# Power_Board.net
KiCad netlist of a schematic drawn in Altium Designer
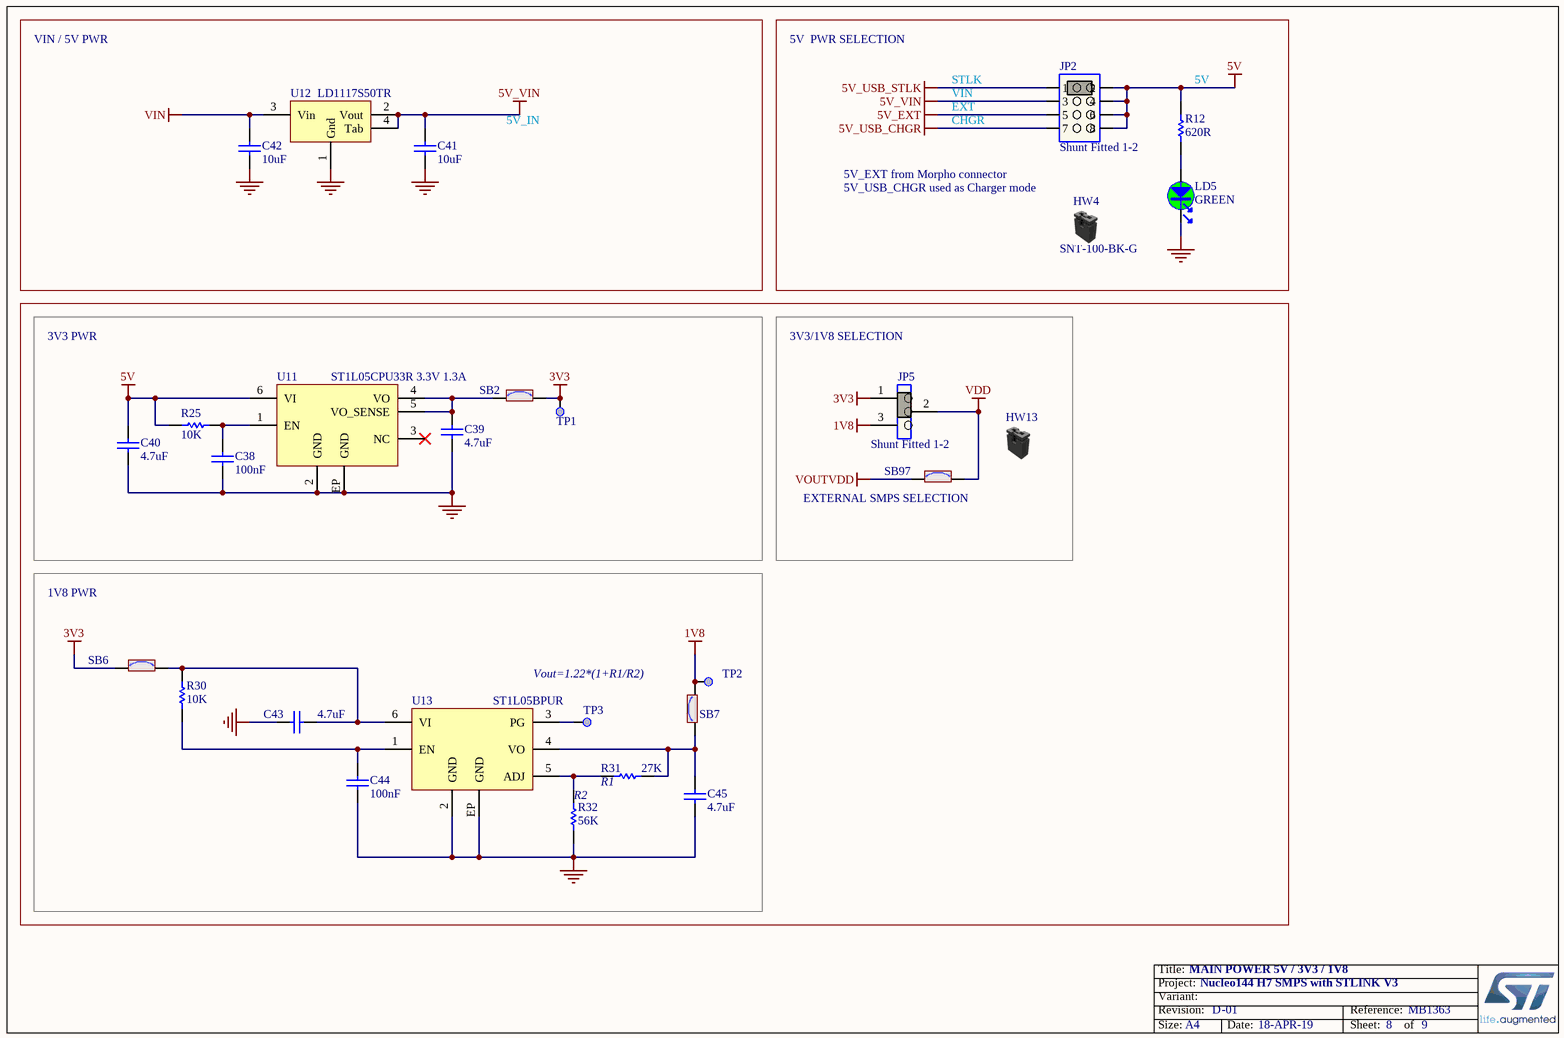
[diagram p0: Power_Board.SchDoc]

(export (version "E")
  (design (tool "Eeschema 10.0.6"))
  (components
    (comp (ref "C38")
      (value "100nF")
      (footprint "C0402")
      (description "Capacitor, MLCC, 100nF, 16V, X7R, 10%, 0402, T=0.5mm")
      (fields
        (field (name "INTERNAL_PART_NUMBER") "MCD-00006")
        (field (name "MANUFACTURER_PART_NUMBER") "CC0402KRX7R7BB104")
        (field (name "PROVIDED_BY") "SUBCO")
      )
      (libsource (lib "MCD_PARTS_database") (part "Capacitor"))
    )
    (comp (ref "C39")
      (value "4.7uF")
      (footprint "C0603")
      (description "Capacitor, MLCC, 4.7µF, 10V, X5R, 20%, 0603, T=0,8mm")
      (fields
        (field (name "INTERNAL_PART_NUMBER") "MCD-01121")
        (field (name "MANUFACTURER_PART_NUMBER") "GRM188R61A475ME15")
        (field (name "PROVIDED_BY") "SUBCO")
      )
      (libsource (lib "MCD_PARTS_database") (part "Capacitor"))
    )
    (comp (ref "C40")
      (value "4.7uF")
      (footprint "C0603")
      (description "Capacitor, MLCC, 4.7uF, 16V, X5R, 20%, 0603, T=0,8mm")
      (fields
        (field (name "INTERNAL_PART_NUMBER") "MCD-00097")
        (field (name "MANUFACTURER_PART_NUMBER") "GRM188R61C475KE11")
        (field (name "PROVIDED_BY") "SUBCO")
      )
      (libsource (lib "MCD_PARTS_database") (part "Capacitor"))
    )
    (comp (ref "C41")
      (value "10uF")
      (footprint "C0805")
      (description "Capacitor, MLCC, 10uF, 25V, X5R, 10%, 0805, T=0,85mm")
      (fields
        (field (name "INTERNAL_PART_NUMBER") "MCD-00014")
        (field (name "MANUFACTURER_PART_NUMBER") "CC0805KRX5R8BB106")
        (field (name "PROVIDED_BY") "SUBCO")
      )
      (libsource (lib "MCD_PARTS_database") (part "Capacitor"))
    )
    (comp (ref "C42")
      (value "10uF")
      (footprint "C0805")
      (description "Capacitor, MLCC, 10uF, 25V, X5R, 10%, 0805, T=0,85mm")
      (fields
        (field (name "INTERNAL_PART_NUMBER") "MCD-00014")
        (field (name "MANUFACTURER_PART_NUMBER") "CC0805KRX5R8BB106")
        (field (name "PROVIDED_BY") "SUBCO")
      )
      (libsource (lib "MCD_PARTS_database") (part "Capacitor"))
    )
    (comp (ref "C43")
      (value "4.7uF")
      (footprint "C0603")
      (description "Capacitor, MLCC, 4.7µF, 10V, X5R, 20%, 0603, T=0,8mm")
      (fields
        (field (name "INTERNAL_PART_NUMBER") "MCD-01121")
        (field (name "MANUFACTURER_PART_NUMBER") "GRM188R61A475ME15")
        (field (name "PROVIDED_BY") "SUBCO")
      )
      (libsource (lib "MCD_PARTS_database") (part "Capacitor"))
    )
    (comp (ref "C44")
      (value "100nF")
      (footprint "C0402")
      (description "Capacitor, MLCC, 100nF, 16V, X7R, 10%, 0402, T=0.5mm")
      (fields
        (field (name "INTERNAL_PART_NUMBER") "MCD-00006")
        (field (name "MANUFACTURER_PART_NUMBER") "CC0402KRX7R7BB104")
        (field (name "PROVIDED_BY") "SUBCO")
      )
      (libsource (lib "MCD_PARTS_database") (part "Capacitor"))
    )
    (comp (ref "C45")
      (value "4.7uF")
      (footprint "C0603")
      (description "Capacitor, MLCC, 4.7µF, 10V, X5R, 20%, 0603, T=0,8mm")
      (fields
        (field (name "INTERNAL_PART_NUMBER") "MCD-01121")
        (field (name "MANUFACTURER_PART_NUMBER") "GRM188R61A475ME15")
        (field (name "PROVIDED_BY") "SUBCO")
      )
      (libsource (lib "MCD_PARTS_database") (part "Capacitor"))
    )
    (comp (ref "HW4")
      (value "SNT-100-BK-G")
      (description "SHUNT 2.54mm BLACK")
      (fields
        (field (name "INTERNAL_PART_NUMBER") "MCD-00043")
        (field (name "MANUFACTURER") "SAMTEC")
        (field (name "PROVIDED_BY") "SUBCO")
      )
      (libsource (lib "MCD_PARTS_database") (part "Shunt Black 2.54mm"))
    )
    (comp (ref "HW13")
      (value "Shunt Black 2.54mm")
      (description "SHUNT 2.54mm BLACK")
      (fields
        (field (name "INTERNAL_PART_NUMBER") "MCD-00043")
        (field (name "MANUFACTURER_PART_NUMBER") "SNT-100-BK-G")
        (field (name "PROVIDED_BY") "SUBCO")
      )
      (libsource (lib "MCD_PARTS_database") (part "Shunt Black 2.54mm"))
    )
    (comp (ref "JP2")
      (value "Shunt Fitted 1-2")
      (footprint "CON_SAMTEC_TSW-104-07-X-D")
      (description "Header, 4x2, 2,54mm, VR, TH, Height 5.84mm/2.54mm - Shunt Fitted 1-2")
      (fields
        (field (name "INTERNAL_PART_NUMBER") "MCD-00686")
        (field (name "MANUFACTURER_PART_NUMBER") "TSW-104-07-x-D")
        (field (name "PROVIDED_BY") "SUBCO")
      )
      (libsource (lib "MCD_PARTS_database") (part "Jumper_Header 4x2 Fitted 1-2"))
    )
    (comp (ref "JP5")
      (value "Shunt Fitted 1-2")
      (footprint "CON_SAMTEC_TSW-103-07-F-S")
      (description "Header, 3x1, 2,54mm, VR, TH, Height 5.84mm/2.54mm - Shunt Fitted 1-2 by default")
      (fields
        (field (name "INTERNAL_PART_NUMBER") "MCD-00684")
        (field (name "MANUFACTURER_PART_NUMBER") "TSW-103-07-F-S")
        (field (name "PROVIDED_BY") "SUBCO")
      )
      (libsource (lib "MCD_PARTS_database") (part "Jumper_Header 3x1 Fitted 1-2"))
    )
    (comp (ref "LD5")
      (value "GREEN")
      (footprint "LED_0603_OSRAM_LG-Q396-PS-35_GREEN_1A2K_H0P4")
      (description "LED Green, 0603 SMD, Forward Voltage Typ=2V, Max=2.5V")
      (fields
        (field (name "INTERNAL_PART_NUMBER") "MCD-00588")
        (field (name "MANUFACTURER_PART_NUMBER") "LG Q396-PS-35")
        (field (name "PROVIDED_BY") "SUBCO")
      )
      (libsource (lib "MCD_PARTS_database") (part "LED_green"))
    )
    (comp (ref "R12")
      (value "620R")
      (footprint "R0603")
      (description "Resistor,620R,0603,1%,1/10W")
      (fields
        (field (name "INTERNAL_PART_NUMBER") "MCD-00500")
        (field (name "MANUFACTURER_PART_NUMBER") "RC0603FR-07620RL")
        (field (name "PROVIDED_BY") "SUBCO")
      )
      (libsource (lib "MCD_PARTS_database") (part "Resistor"))
    )
    (comp (ref "R25")
      (value "10K")
      (footprint "R0402")
      (description "Resistor,10K,0402,1%,1/16W")
      (fields
        (field (name "INTERNAL_PART_NUMBER") "MCD-00053")
        (field (name "MANUFACTURER_PART_NUMBER") "RC0402FR-0710KL")
        (field (name "PROVIDED_BY") "SUBCO")
      )
      (libsource (lib "MCD_PARTS_database") (part "Resistor"))
    )
    (comp (ref "R30")
      (value "10K")
      (footprint "R0402")
      (description "Resistor,10K,0402,1%,1/16W")
      (fields
        (field (name "INTERNAL_PART_NUMBER") "MCD-00053")
        (field (name "MANUFACTURER_PART_NUMBER") "RC0402FR-0710KL")
        (field (name "PROVIDED_BY") "SUBCO")
      )
      (libsource (lib "MCD_PARTS_database") (part "Resistor"))
    )
    (comp (ref "R31")
      (value "27K")
      (footprint "R0402")
      (description "Resistor,27K,0402,1%,1/16W")
      (fields
        (field (name "INTERNAL_PART_NUMBER") "MCD-00443")
        (field (name "MANUFACTURER_PART_NUMBER") "RC0402FR-0727KL")
        (field (name "PROVIDED_BY") "SUBCO")
      )
      (libsource (lib "MCD_PARTS_database") (part "Resistor"))
    )
    (comp (ref "R32")
      (value "56K")
      (footprint "R0402")
      (description "Resistor,56K,0402,1%,1/16W")
      (fields
        (field (name "INTERNAL_PART_NUMBER") "MCD-00493")
        (field (name "MANUFACTURER_PART_NUMBER") "RC0402FR-0756KL")
        (field (name "PROVIDED_BY") "SUBCO")
      )
      (libsource (lib "MCD_PARTS_database") (part "Resistor"))
    )
    (comp (ref "SB2")
      (value "SB_ON")
      (footprint "SOLDER-BRIDGE_R0603-0R")
      (description "Solder Bridge ON")
      (fields
        (field (name "INTERNAL_PART_NUMBER") "MCD-00071")
        (field (name "MANUFACTURER_PART_NUMBER") "RC0603JR-070RL")
        (field (name "PROVIDED_BY") "SUBCO")
      )
      (libsource (lib "MCD_PARTS_database") (part "SB_ON"))
    )
    (comp (ref "SB6")
      (value "SB_ON")
      (footprint "SOLDER-BRIDGE_R0603-0R")
      (description "Solder Bridge ON")
      (fields
        (field (name "INTERNAL_PART_NUMBER") "MCD-00071")
        (field (name "MANUFACTURER_PART_NUMBER") "RC0603JR-070RL")
        (field (name "PROVIDED_BY") "SUBCO")
      )
      (libsource (lib "MCD_PARTS_database") (part "SB_ON"))
    )
    (comp (ref "SB7")
      (value "SB_ON")
      (footprint "SOLDER-BRIDGE_R0603-0R")
      (description "Solder Bridge ON")
      (fields
        (field (name "INTERNAL_PART_NUMBER") "MCD-00071")
        (field (name "MANUFACTURER_PART_NUMBER") "RC0603JR-070RL")
        (field (name "PROVIDED_BY") "SUBCO")
      )
      (libsource (lib "") (part "SB_ON_1"))
    )
    (comp (ref "SB97")
      (value "SB_ON")
      (footprint "SOLDER-BRIDGE_R0603-0R")
      (description "Solder Bridge ON")
      (fields
        (field (name "INTERNAL_PART_NUMBER") "MCD-00071")
        (field (name "MANUFACTURER_PART_NUMBER") "RC0603JR-070RL")
        (field (name "PROVIDED_BY") "SUBCO")
      )
      (libsource (lib "MCD_PARTS_database") (part "SB_ON"))
    )
    (comp (ref "TP1")
      (value "Test Point")
      (footprint "TP_SMD_1MM")
      (description "Test Point 1mm")
      (fields (field (name "INTERNAL_PART_NUMBER") "MCD-00074") (field (name "MANUFACTURER") "n/a"))
      (libsource (lib "MCD_PARTS_database") (part "Test Point"))
    )
    (comp (ref "TP2")
      (value "Test Point")
      (footprint "TP_SMD_1MM")
      (description "Test Point 1mm")
      (fields
        (field (name "INTERNAL_PART_NUMBER") "MCD-00074")
        (field (name "MANUFACTURER_PART_NUMBER") "n/a")
      )
      (libsource (lib "") (part "Test Point_1"))
    )
    (comp (ref "TP3")
      (value "Test Point")
      (footprint "TP_SMD_1MM")
      (description "Test Point 1mm")
      (fields (field (name "INTERNAL_PART_NUMBER") "MCD-00074") (field (name "MANUFACTURER") "n/a"))
      (libsource (lib "") (part "Test Point_1"))
    )
    (comp (ref "U11")
      (value "ST1L05CPU33R 3.3V 1.3A")
      (footprint "ICC_DFN6-EPAD_3X3_P095")
      (description "LDO, 3.3V, 1.3A, Very low quiescent current BiCMOS voltage regulator")
      (fields
        (field (name "INTERNAL_PART_NUMBER") "MCD-01025")
        (field (name "MANUFACTURER_PART_NUMBER") "ST1L05CPU33R")
        (field (name "PROVIDED_BY") "SUBCO with ST control")
      )
      (libsource (lib "MCD_PARTS_database") (part "ST1L05CPU33R"))
    )
    (comp (ref "U12")
      (value "LD1117S50TR")
      (footprint "REG_SOT223-TAB")
      (description "IC REG LDO 5V 0.8A SOT223")
      (fields
        (field (name "INTERNAL_PART_NUMBER") "MCD-00088")
        (field (name "MANUFACTURER") "STMICROELECTRONICS")
        (field (name "PROVIDED_BY") "SUBCO with ST control")
      )
      (libsource (lib "MCD_PARTS_database") (part "LD1117S50TR"))
    )
    (comp (ref "U13")
      (value "ST1L05BPUR")
      (footprint "ICC_DFN6-EPAD_3X3_P095")
      (description "LDO Linear Voltage Regulator IC Positive Adjustable 1 Output Adjustable 1.3A 6-DFN (3x3)")
      (fields
        (field (name "INTERNAL_PART_NUMBER") "MCD-00581")
        (field (name "MANUFACTURER") "STMICROELECTRONICS")
        (field (name "PROVIDED_BY") "SUBCO with ST control")
      )
      (libsource (lib "MCD_PARTS_database") (part "ST1L05BPUR"))
    )
  )
  (nets
    (net (code "1") (name "1V8") (class "Default")
      (node (ref "JP5") (pin "3") (pinfunction "3_3") (pintype "passive"))
      (node (ref "SB7") (pin "2") (pinfunction "2_2") (pintype "passive"))
      (node (ref "TP2") (pin "1") (pinfunction "1_1") (pintype "passive"))
    )
    (net (code "2") (name "3V3") (class "Default")
      (node (ref "JP5") (pin "1") (pinfunction "1_1") (pintype "passive"))
      (node (ref "SB2") (pin "2") (pinfunction "2_2") (pintype "passive"))
      (node (ref "SB6") (pin "1") (pinfunction "1_1") (pintype "passive"))
      (node (ref "TP1") (pin "1") (pinfunction "1_1") (pintype "passive"))
    )
    (net (code "3") (name "5V") (class "Default")
      (node (ref "C40") (pin "2") (pinfunction "2_2") (pintype "passive"))
      (node (ref "JP2") (pin "2") (pinfunction "2_2") (pintype "passive"))
      (node (ref "JP2") (pin "4") (pinfunction "4_4") (pintype "passive"))
      (node (ref "JP2") (pin "6") (pinfunction "6_6") (pintype "passive"))
      (node (ref "JP2") (pin "8") (pinfunction "8_8") (pintype "passive"))
      (node (ref "R12") (pin "2") (pinfunction "2_2") (pintype "passive"))
      (node (ref "R25") (pin "2") (pinfunction "2_2") (pintype "passive"))
      (node (ref "U11") (pin "6") (pinfunction "VI_6") (pintype "passive"))
    )
    (net (code "4") (name "5V_EXT") (class "Default")
      (node (ref "JP2") (pin "5") (pinfunction "5_5") (pintype "passive"))
    )
    (net (code "5") (name "5V_USB_CHGR") (class "Default")
      (node (ref "JP2") (pin "7") (pinfunction "7_7") (pintype "passive"))
    )
    (net (code "6") (name "5V_USB_STLK") (class "Default")
      (node (ref "JP2") (pin "1") (pinfunction "1_1") (pintype "passive"))
    )
    (net (code "7") (name "5V_VIN") (class "Default")
      (node (ref "C41") (pin "2") (pinfunction "2_2") (pintype "passive"))
      (node (ref "JP2") (pin "3") (pinfunction "3_3") (pintype "passive"))
      (node (ref "U12") (pin "2") (pinfunction "Vout_2") (pintype "passive"))
      (node (ref "U12") (pin "4") (pinfunction "Tab_4") (pintype "passive"))
    )
    (net (code "8") (name "GND") (class "Default")
      (node (ref "C38") (pin "2") (pinfunction "2_2") (pintype "passive"))
      (node (ref "C39") (pin "1") (pinfunction "1_1") (pintype "passive"))
      (node (ref "C40") (pin "1") (pinfunction "1_1") (pintype "passive"))
      (node (ref "C41") (pin "1") (pinfunction "1_1") (pintype "passive"))
      (node (ref "C42") (pin "1") (pinfunction "1_1") (pintype "passive"))
      (node (ref "C43") (pin "2") (pinfunction "2_2") (pintype "passive"))
      (node (ref "C44") (pin "2") (pinfunction "2_2") (pintype "passive"))
      (node (ref "C45") (pin "1") (pinfunction "1_1") (pintype "passive"))
      (node (ref "LD5") (pin "2") (pintype "passive"))
      (node (ref "R32") (pin "1") (pinfunction "1_1") (pintype "passive"))
      (node (ref "U11") (pin "2") (pinfunction "GND_2") (pintype "passive"))
      (node (ref "U11") (pin "EP") (pinfunction "GND_EP") (pintype "passive"))
      (node (ref "U12") (pin "1") (pinfunction "Gnd_1") (pintype "passive"))
      (node (ref "U13") (pin "2") (pinfunction "GND_2") (pintype "passive"))
      (node (ref "U13") (pin "EP") (pinfunction "GND_EP") (pintype "passive"))
    )
    (net (code "9") (name "Net-(LD5-Pad1)") (class "Default")
      (node (ref "LD5") (pin "1") (pintype "passive"))
      (node (ref "R12") (pin "1") (pinfunction "1_1") (pintype "passive"))
    )
    (net (code "10") (name "Net-(U11-EN)") (class "Default")
      (node (ref "C38") (pin "1") (pinfunction "1_1") (pintype "passive"))
      (node (ref "R25") (pin "1") (pinfunction "1_1") (pintype "passive"))
      (node (ref "U11") (pin "1") (pinfunction "EN_1") (pintype "passive"))
    )
    (net (code "11") (name "Net-(U11-VO)") (class "Default")
      (node (ref "C39") (pin "2") (pinfunction "2_2") (pintype "passive"))
      (node (ref "SB2") (pin "1") (pinfunction "1_1") (pintype "passive"))
      (node (ref "U11") (pin "4") (pinfunction "VO_4") (pintype "passive"))
      (node (ref "U11") (pin "5") (pinfunction "VO_SENSE_5") (pintype "passive"))
    )
    (net (code "12") (name "Net-(U13-ADJ)") (class "Default")
      (node (ref "R31") (pin "2") (pinfunction "2_2") (pintype "passive"))
      (node (ref "R32") (pin "2") (pinfunction "2_2") (pintype "passive"))
      (node (ref "U13") (pin "5") (pinfunction "ADJ_5") (pintype "passive"))
    )
    (net (code "13") (name "Net-(U13-EN)") (class "Default")
      (node (ref "C44") (pin "1") (pinfunction "1_1") (pintype "passive"))
      (node (ref "R30") (pin "2") (pinfunction "2_2") (pintype "passive"))
      (node (ref "U13") (pin "1") (pinfunction "EN_1") (pintype "passive"))
    )
    (net (code "14") (name "Net-(U13-PG)") (class "Default")
      (node (ref "TP3") (pin "1") (pinfunction "1_1") (pintype "passive"))
      (node (ref "U13") (pin "3") (pinfunction "PG_3") (pintype "passive"))
    )
    (net (code "15") (name "Net-(U13-VI)") (class "Default")
      (node (ref "C43") (pin "1") (pinfunction "1_1") (pintype "passive"))
      (node (ref "R30") (pin "1") (pinfunction "1_1") (pintype "passive"))
      (node (ref "SB6") (pin "2") (pinfunction "2_2") (pintype "passive"))
      (node (ref "U13") (pin "6") (pinfunction "VI_6") (pintype "passive"))
    )
    (net (code "16") (name "Net-(U13-VO)") (class "Default")
      (node (ref "C45") (pin "2") (pinfunction "2_2") (pintype "passive"))
      (node (ref "R31") (pin "1") (pinfunction "1_1") (pintype "passive"))
      (node (ref "SB7") (pin "1") (pinfunction "1_1") (pintype "passive"))
      (node (ref "U13") (pin "4") (pinfunction "VO_4") (pintype "passive"))
    )
    (net (code "17") (name "VDD") (class "Default")
      (node (ref "JP5") (pin "2") (pinfunction "2_2") (pintype "passive"))
      (node (ref "SB97") (pin "2") (pinfunction "2_2") (pintype "passive"))
    )
    (net (code "18") (name "VIN") (class "Default")
      (node (ref "C42") (pin "2") (pinfunction "2_2") (pintype "passive"))
      (node (ref "U12") (pin "3") (pinfunction "Vin_3") (pintype "passive"))
    )
    (net (code "19") (name "VOUTVDD") (class "Default")
      (node (ref "SB97") (pin "1") (pinfunction "1_1") (pintype "passive"))
    )
    (net (code "20") (name "unconnected-(U11-NC-Pad3)") (class "Default")
      (node (ref "U11") (pin "3") (pinfunction "NC_3") (pintype "passive+no_connect"))
    )
  )
)
